# Motor_Controller_Interface.net
KiCad netlist of a schematic drawn in Altium Designer
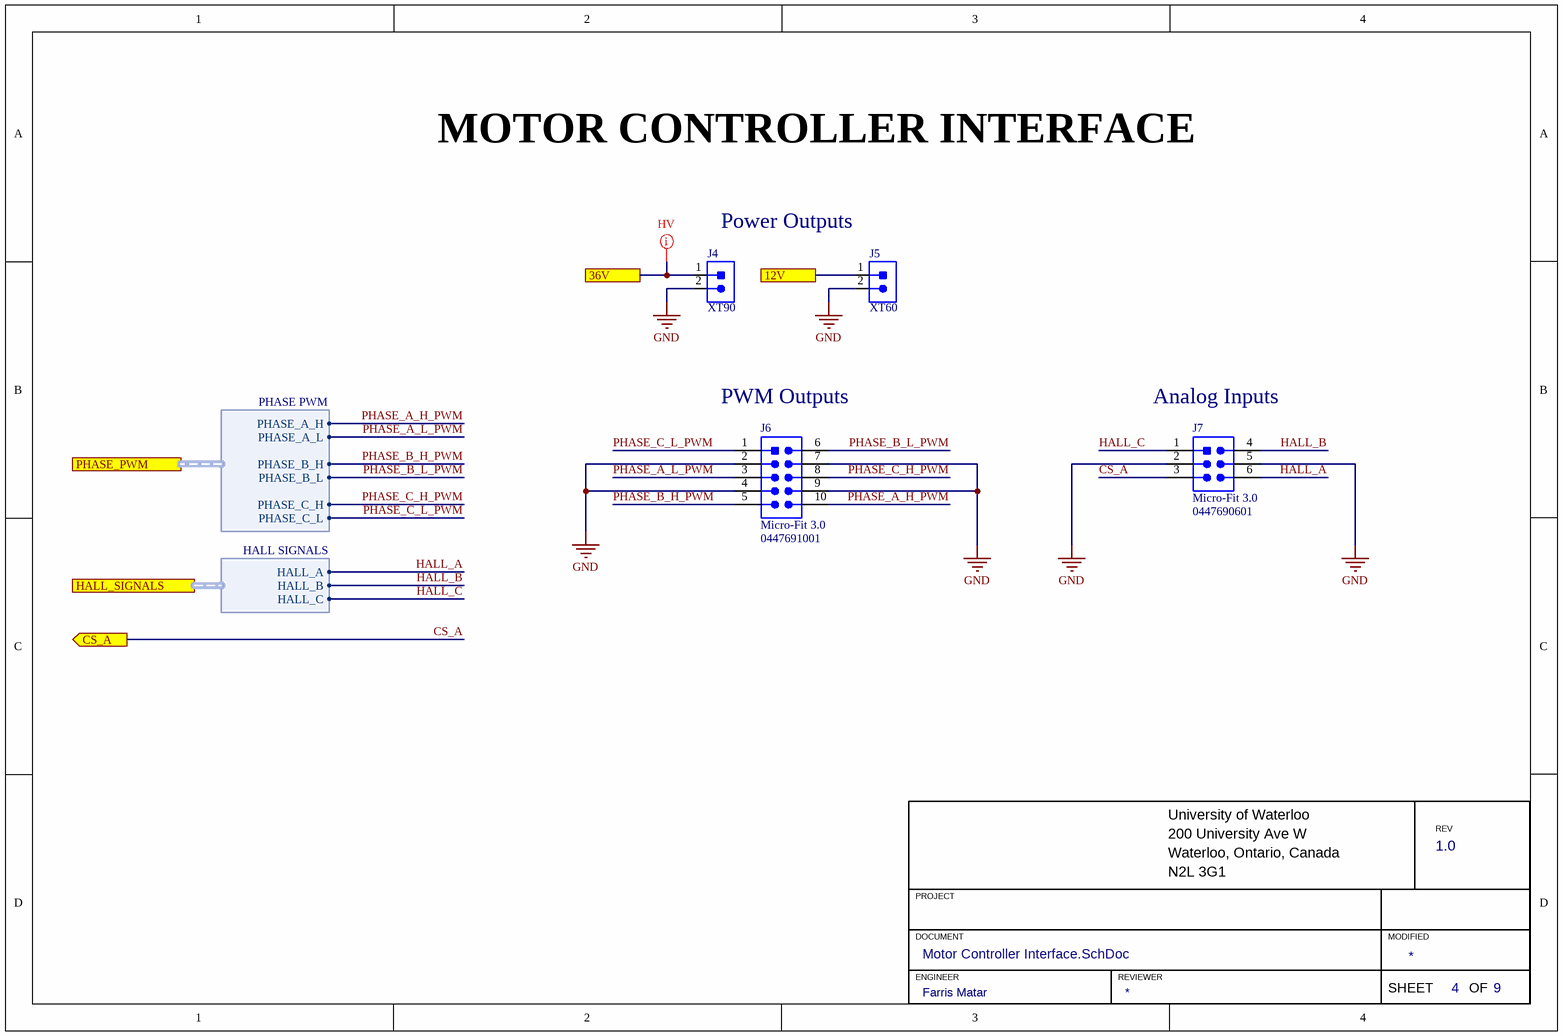
[diagram p0: Motor Controller Interface.SchDoc]

(export (version "E")
  (design (tool "Eeschema 10.0.6"))
  (components
    (comp (ref "J4")
      (value "CON_2POS_XT90")
      (footprint "XT90")
      (description "HIGH QUALITY GOLD PLATED XT90 MA")
      (fields (field (name "PACKAGE/FOOTPRINT") "XT90"))
      (libsource (lib "Personal_Schematic_Library_2022") (part "CON_2POS_XT90"))
    )
    (comp (ref "J5")
      (value "CON_2POS_XT60")
      (footprint "XT60")
      (description "XT60 CONNECTORS MALE/FEMALE PAIR")
      (fields (field (name "PACKAGE/FOOTPRINT") "XT60"))
      (libsource (lib "Personal_Schematic_Library_2022") (part "CON_2POS_XT60"))
    )
    (comp (ref "J6")
      (value "0447691001")
      (footprint "MOLEX-0447691001")
      (description "CONN RCPT 10POS 0.118 TIN PCB")
      (fields
        (field (name "FAMILY") "Micro-Fit 3.0")
        (field (name "MANUFACTURER PART NUMBER 1") "0447691001")
      )
      (libsource (lib "UWRT_Schematic_Library_2020") (part "CON_MOLEX-RCPT_5x2_TH"))
    )
    (comp (ref "J7")
      (value "0447690601")
      (footprint "MOLEX-0447690601")
      (description "CONN RCPT 6POS 0.118 TIN PCB")
      (fields
        (field (name "FAMILY") "Micro-Fit 3.0")
        (field (name "MANUFACTURER PART NUMBER 1") "0447690601")
      )
      (libsource (lib "UWRT_Schematic_Library_2020") (part "CON_MOLEX-RCPT_3x2_TH"))
    )
  )
  (nets
    (net (code "5") (name "/12V") (class "Default")
      (node (ref "J5") (pin "1") (pinfunction "1_1") (pintype "passive"))
    )
    (net (code "6") (name "/36V") (class "Default")
      (node (ref "J4") (pin "1") (pinfunction "1_1") (pintype "passive"))
    )
    (net (code "7") (name "/CS_A") (class "Default")
      (node (ref "J7") (pin "3") (pinfunction "3_3") (pintype "passive"))
    )
    (net (code "8") (name "/HALL_A") (class "Default")
      (node (ref "J7") (pin "6") (pinfunction "6_6") (pintype "passive"))
    )
    (net (code "9") (name "/HALL_B") (class "Default")
      (node (ref "J7") (pin "4") (pinfunction "4_4") (pintype "passive"))
    )
    (net (code "10") (name "/HALL_C") (class "Default")
      (node (ref "J7") (pin "1") (pinfunction "1_1") (pintype "passive"))
    )
    (net (code "11") (name "/PHASE_A_H_PWM") (class "Default")
      (node (ref "J6") (pin "10") (pinfunction "10_10") (pintype "passive"))
    )
    (net (code "12") (name "/PHASE_A_L_PWM") (class "Default")
      (node (ref "J6") (pin "3") (pinfunction "3_3") (pintype "passive"))
    )
    (net (code "13") (name "/PHASE_B_H_PWM") (class "Default")
      (node (ref "J6") (pin "5") (pinfunction "5_5") (pintype "passive"))
    )
    (net (code "14") (name "/PHASE_B_L_PWM") (class "Default")
      (node (ref "J6") (pin "6") (pinfunction "6_6") (pintype "passive"))
    )
    (net (code "15") (name "/PHASE_C_H_PWM") (class "Default")
      (node (ref "J6") (pin "8") (pinfunction "8_8") (pintype "passive"))
    )
    (net (code "16") (name "/PHASE_C_L_PWM") (class "Default")
      (node (ref "J6") (pin "1") (pinfunction "1_1") (pintype "passive"))
    )
    (net (code "19") (name "GND") (class "Default")
      (node (ref "J4") (pin "2") (pinfunction "2_2") (pintype "passive"))
      (node (ref "J5") (pin "2") (pinfunction "2_2") (pintype "passive"))
      (node (ref "J6") (pin "2") (pinfunction "2_2") (pintype "passive"))
      (node (ref "J6") (pin "4") (pinfunction "4_4") (pintype "passive"))
      (node (ref "J6") (pin "7") (pinfunction "7_7") (pintype "passive"))
      (node (ref "J6") (pin "9") (pinfunction "9_9") (pintype "passive"))
      (node (ref "J7") (pin "2") (pinfunction "2_2") (pintype "passive"))
      (node (ref "J7") (pin "5") (pinfunction "5_5") (pintype "passive"))
    )
  )
)
